# keyboard-line.net
KiCad netlist of a schematic drawn in EasyEDA
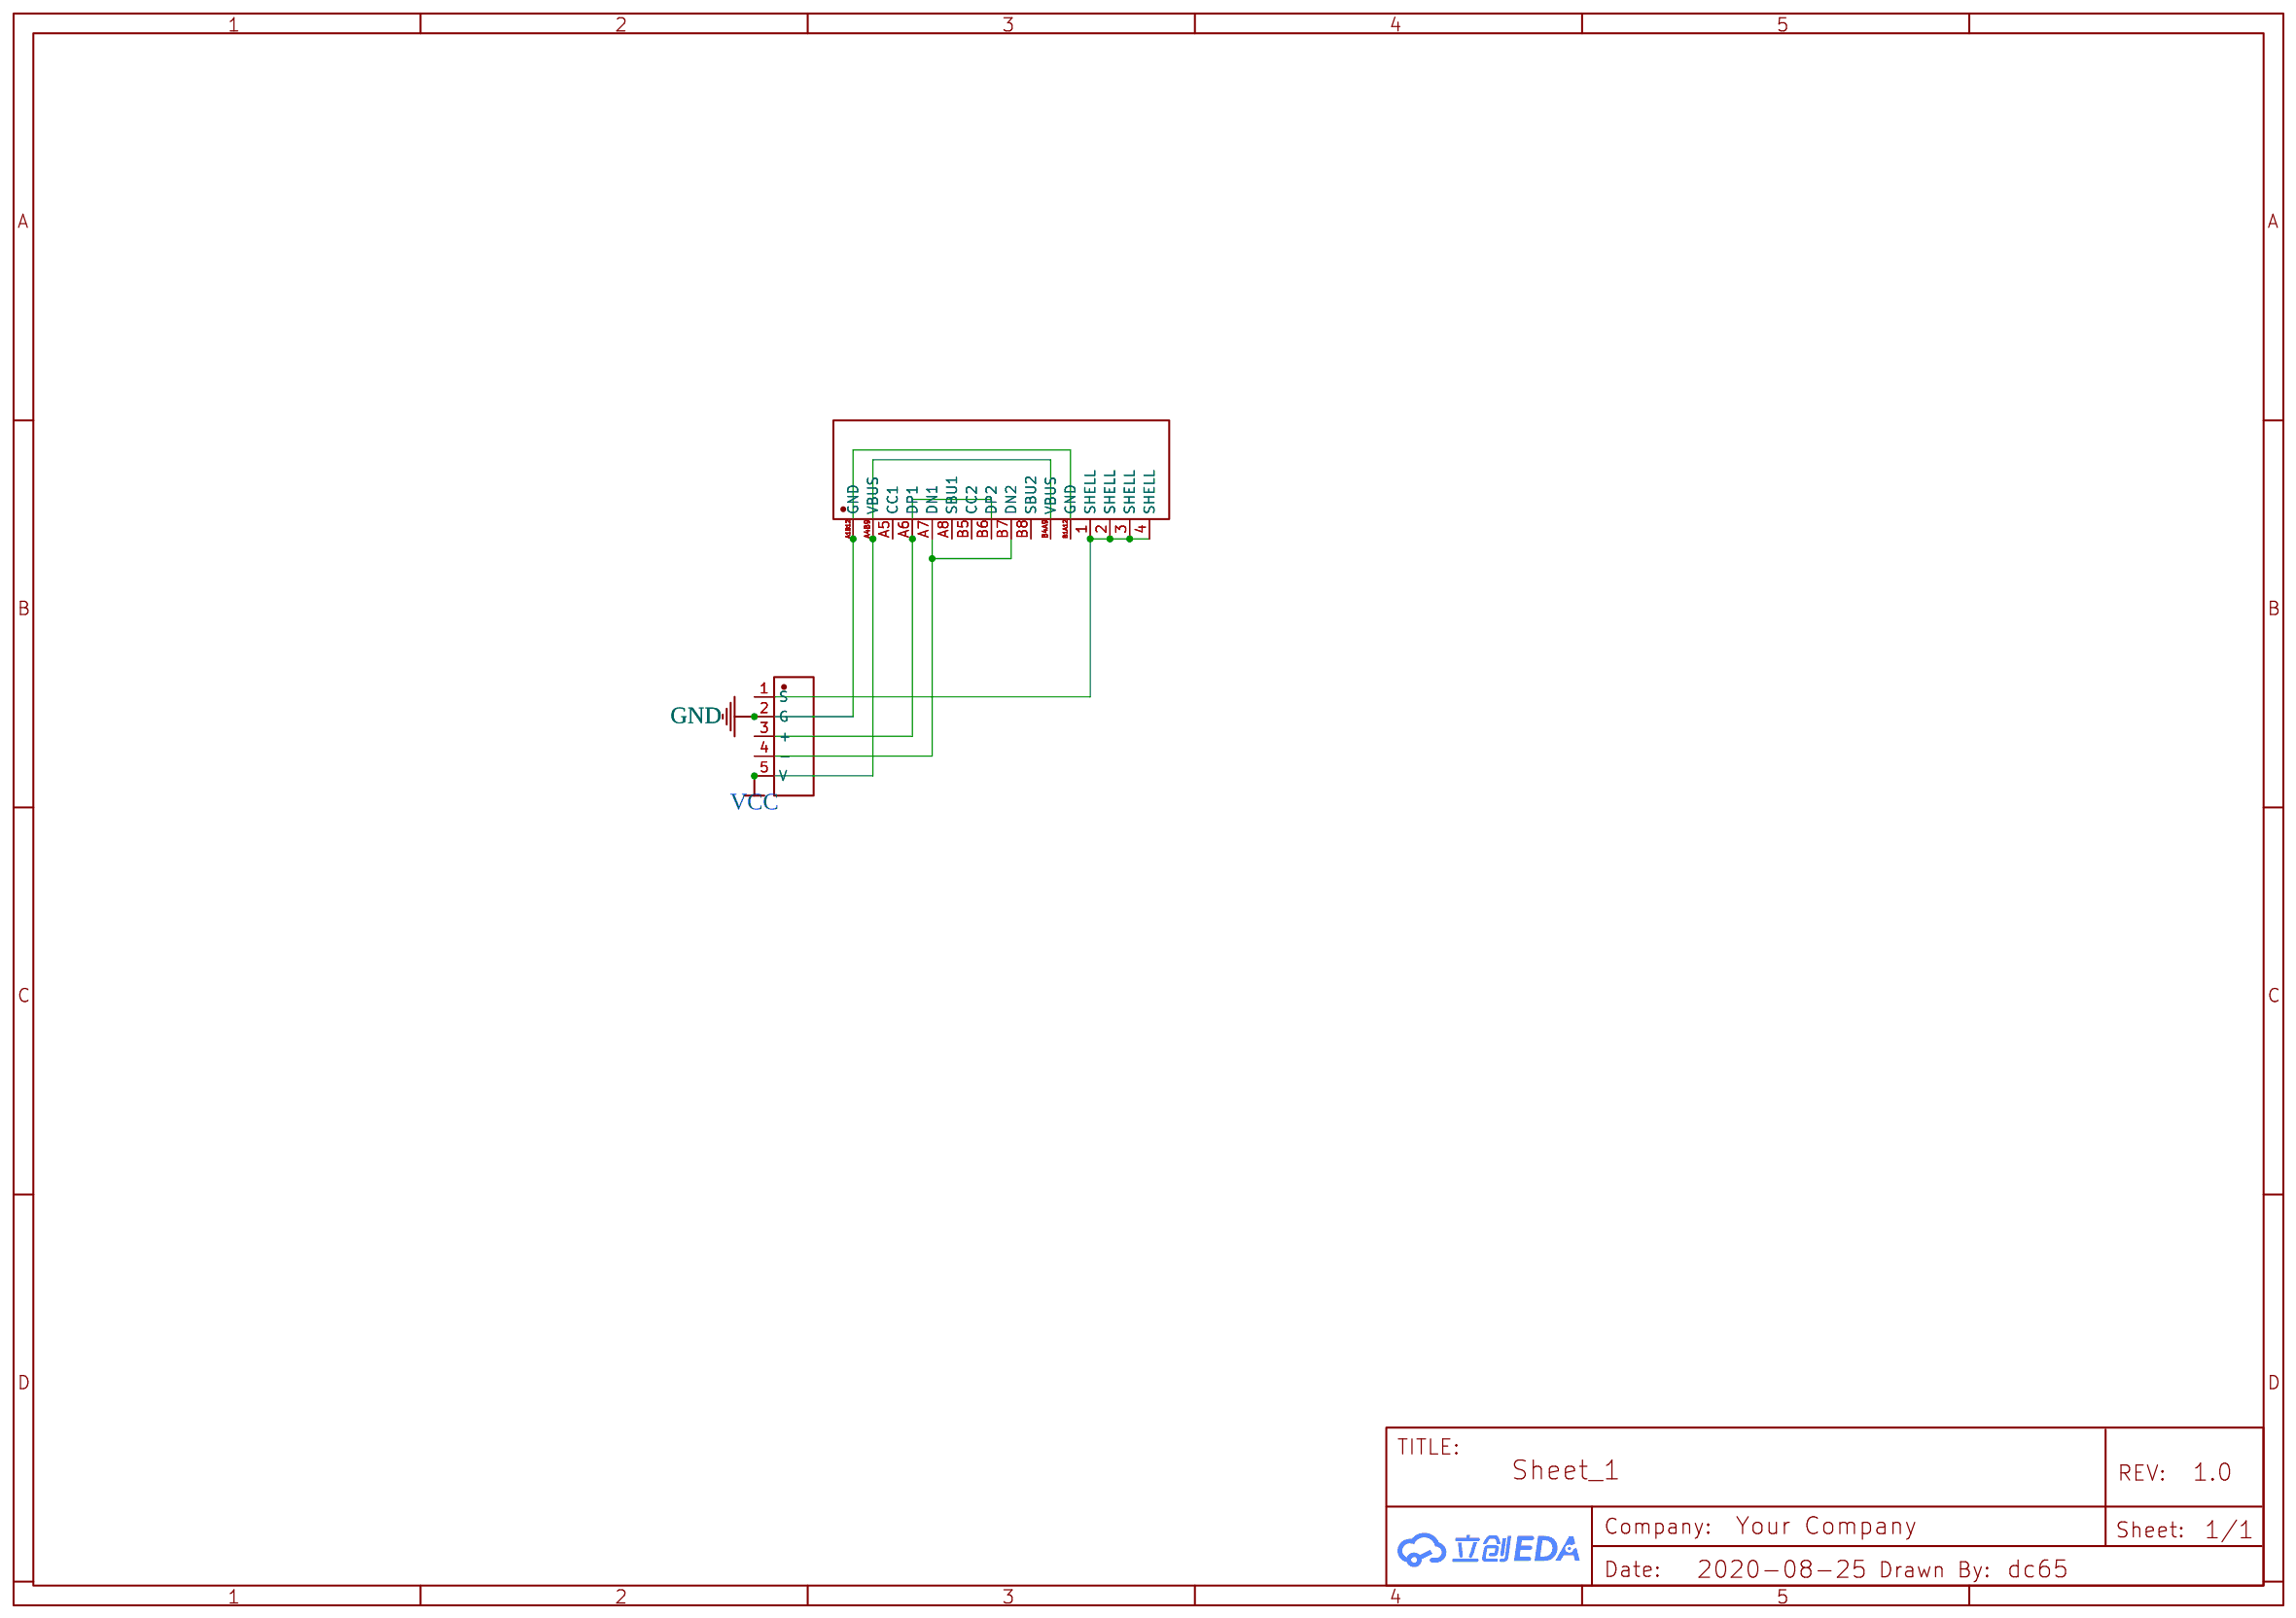
[diagram p0: schematic sheet]

(export (version "E")
  (design (tool "Eeschema 10.0.6"))
  (components
    (comp (ref "CN1")
      (value "ph2.0-50-无丝印")
      (fields
        (field (name "BOM_Manufacturer Part") "A2008WR-5P")
        (field (name "BOM_Supplier Part") "C273103")
      )
      (libsource (lib "") (part "ph2.0-50-无丝印"))
    )
    (comp (ref "USB1")
      (value "TYPE-C16PIN")
      (fields (field (name "BOM_Supplier Part") "C393939"))
      (libsource (lib "") (part "TYPE-C16PIN"))
    )
  )
  (nets
    (net (code "1") (name "GND") (class "Default")
      (node (ref "CN1") (pin "2") (pinfunction "G_2") (pintype "unspecified"))
      (node (ref "USB1") (pin "A1B12") (pinfunction "GND_A1B12") (pintype "unspecified"))
      (node (ref "USB1") (pin "B1A12") (pinfunction "GND_B1A12") (pintype "unspecified"))
    )
    (net (code "2") (name "Net-(CN1-+)") (class "Default")
      (node (ref "CN1") (pin "3") (pinfunction "+_3") (pintype "unspecified"))
      (node (ref "USB1") (pin "A6") (pinfunction "DP1_A6") (pintype "unspecified"))
      (node (ref "USB1") (pin "B6") (pinfunction "DP2_B6") (pintype "unspecified"))
    )
    (net (code "3") (name "Net-(CN1--)") (class "Default")
      (node (ref "CN1") (pin "4") (pinfunction "-_4") (pintype "unspecified"))
      (node (ref "USB1") (pin "A7") (pinfunction "DN1_A7") (pintype "unspecified"))
      (node (ref "USB1") (pin "B7") (pinfunction "DN2_B7") (pintype "unspecified"))
    )
    (net (code "4") (name "Net-(CN1-S)") (class "Default")
      (node (ref "CN1") (pin "1") (pinfunction "S_1") (pintype "unspecified"))
      (node (ref "USB1") (pin "1") (pinfunction "SHELL_1") (pintype "unspecified"))
      (node (ref "USB1") (pin "2") (pinfunction "SHELL_2") (pintype "unspecified"))
      (node (ref "USB1") (pin "3") (pinfunction "SHELL_3") (pintype "unspecified"))
      (node (ref "USB1") (pin "4") (pinfunction "SHELL_4") (pintype "unspecified"))
    )
    (net (code "5") (name "VCC") (class "Default")
      (node (ref "CN1") (pin "5") (pinfunction "V_5") (pintype "unspecified"))
      (node (ref "USB1") (pin "A4B9") (pinfunction "VBUS_A4B9") (pintype "unspecified"))
      (node (ref "USB1") (pin "B4A9") (pinfunction "VBUS_B4A9") (pintype "unspecified"))
    )
    (net (code "6") (name "unconnected-(USB1-CC1-PadA5)") (class "Default")
      (node (ref "USB1") (pin "A5") (pinfunction "CC1_A5") (pintype "unspecified"))
    )
    (net (code "7") (name "unconnected-(USB1-CC2-PadB5)") (class "Default")
      (node (ref "USB1") (pin "B5") (pinfunction "CC2_B5") (pintype "unspecified"))
    )
    (net (code "8") (name "unconnected-(USB1-SBU1-PadA8)") (class "Default")
      (node (ref "USB1") (pin "A8") (pinfunction "SBU1_A8") (pintype "unspecified"))
    )
    (net (code "9") (name "unconnected-(USB1-SBU2-PadB8)") (class "Default")
      (node (ref "USB1") (pin "B8") (pinfunction "SBU2_B8") (pintype "unspecified"))
    )
  )
)
